# 5_SCS.net
KiCad netlist of a schematic drawn in Altium Designer
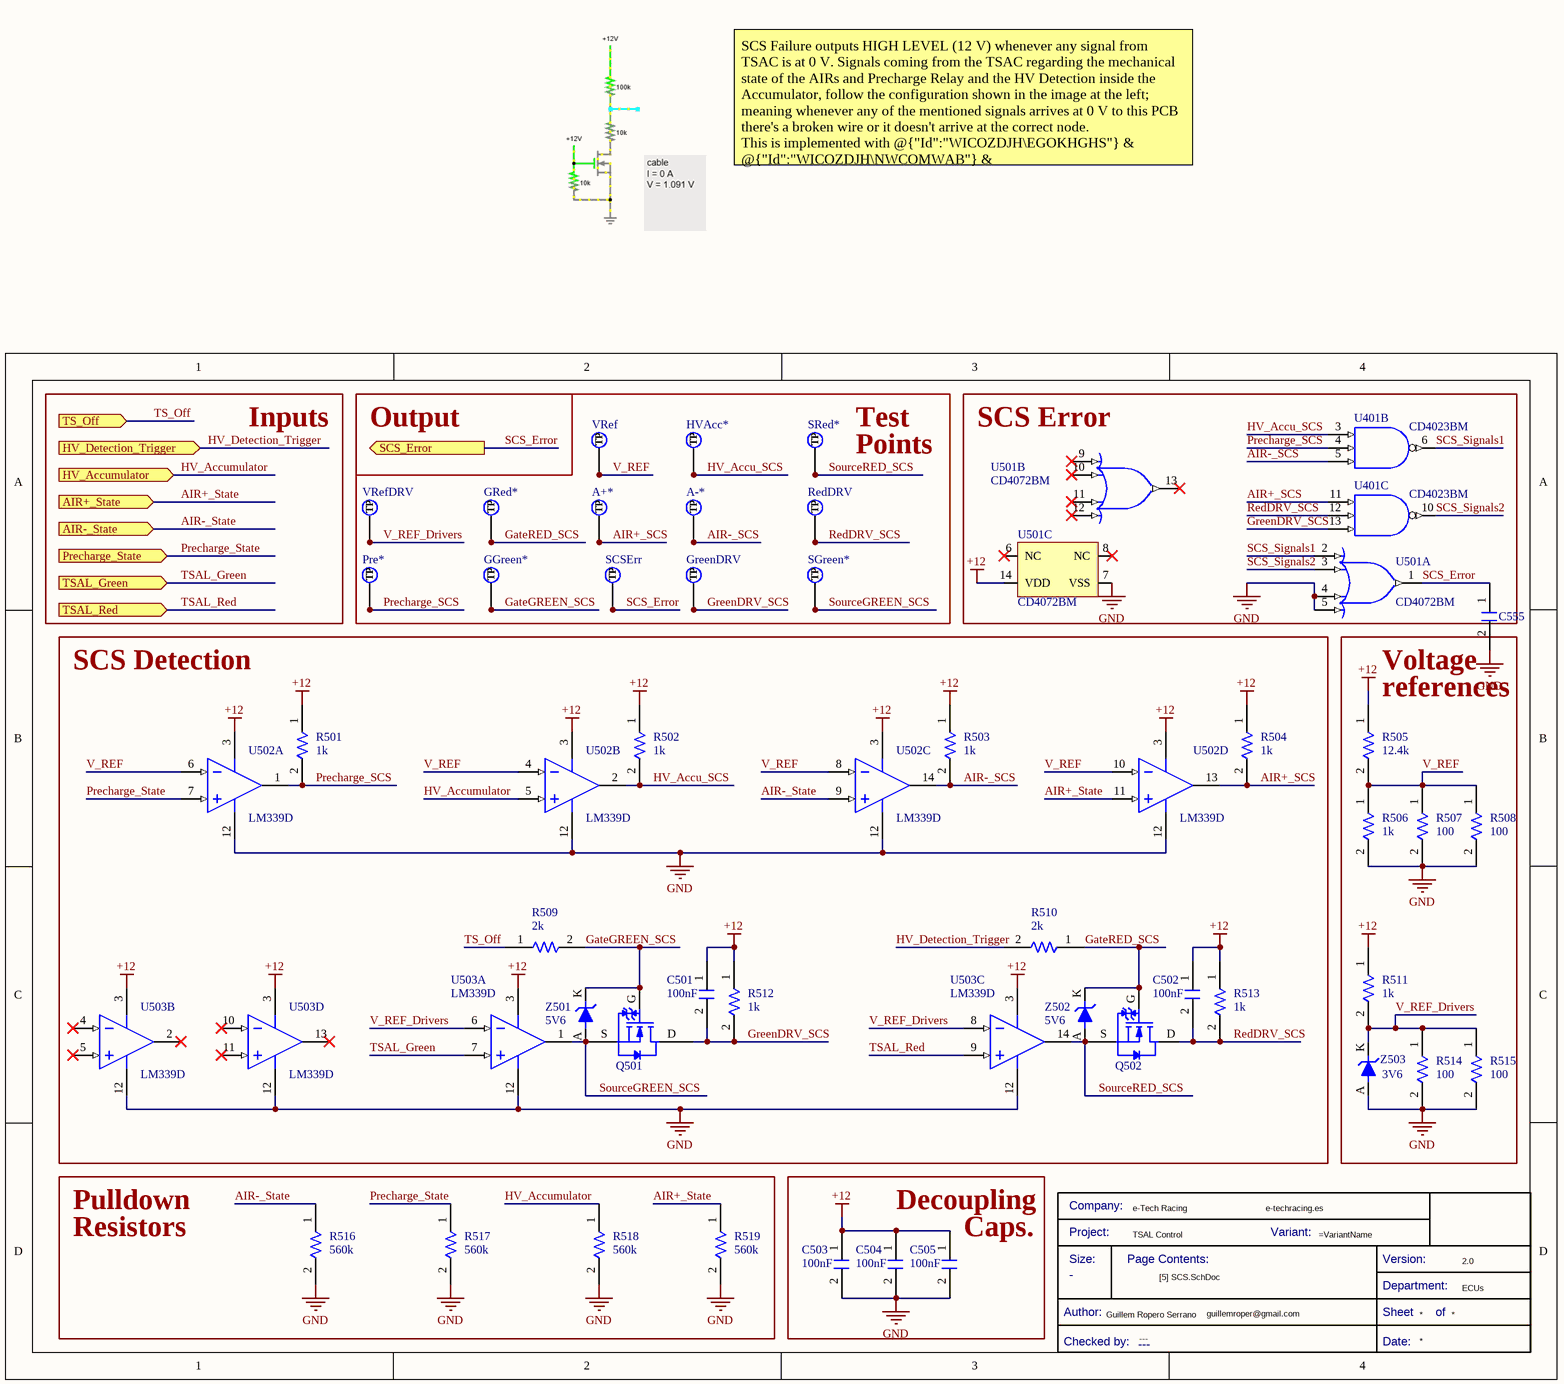
[diagram p0: [5] SCS.SchDoc]

(export (version "E")
  (design (tool "Eeschema 10.0.6"))
  (components
    (comp (ref "A+*")
      (value "TestPoint")
      (footprint "TestPoint")
      (description "Test Point 1x1 mm")
      (fields (field (name ".SCHCHECK") "GP") (field (name ".CREATOR") "GP") (field (name ".PCBCHECK") "GP"))
      (libsource (lib "EMEA- E-Tech Racing- I'Escola d'Enginyeria de Barcelona Est") (part "TestPoint"))
    )
    (comp (ref "A-*")
      (value "TestPoint")
      (footprint "TestPoint")
      (description "Test Point 1x1 mm")
      (fields (field (name ".SCHCHECK") "GP") (field (name ".CREATOR") "GP") (field (name ".PCBCHECK") "GP"))
      (libsource (lib "EMEA- E-Tech Racing- I'Escola d'Enginyeria de Barcelona Est") (part "TestPoint"))
    )
    (comp (ref "C501")
      (value "100nF")
      (footprint "C0805FNPC-R")
      (description "Cap, 0.1ΜF, 50V, 10%, X7R, 0805")
      (fields
        (field (name "TOLERANCE") "10%")
        (field (name "Comment") "C100n-50V-0805FNPC-X7R")
        (field (name ".CREATOR") "DR")
      )
      (libsource (lib "EMEA- E-Tech Racing- I'Escola d'Enginyeria de Barcelona Est") (part "C100p-50V-0805FNPC-C0G/NP0"))
    )
    (comp (ref "C502")
      (value "100nF")
      (footprint "C0805FNPC-R")
      (description "Cap, 0.1ΜF, 50V, 10%, X7R, 0805")
      (fields
        (field (name "TOLERANCE") "10%")
        (field (name "Comment") "C100n-50V-0805FNPC-X7R")
        (field (name ".CREATOR") "DR")
      )
      (libsource (lib "EMEA- E-Tech Racing- I'Escola d'Enginyeria de Barcelona Est") (part "C100p-50V-0805FNPC-C0G/NP0"))
    )
    (comp (ref "C503")
      (value "100nF")
      (footprint "C0805FNPC-R")
      (description "Cap, 0.1ΜF, 50V, 10%, X7R, 0805")
      (fields
        (field (name "TOLERANCE") "10%")
        (field (name "Comment") "C100n-50V-0805FNPC-X7R")
        (field (name ".CREATOR") "DR")
      )
      (libsource (lib "EMEA- E-Tech Racing- I'Escola d'Enginyeria de Barcelona Est") (part "C100p-50V-0805FNPC-C0G/NP0"))
    )
    (comp (ref "C504")
      (value "100nF")
      (footprint "C0805FNPC-R")
      (description "Cap, 0.1ΜF, 50V, 10%, X7R, 0805")
      (fields
        (field (name "TOLERANCE") "10%")
        (field (name "Comment") "C100n-50V-0805FNPC-X7R")
        (field (name ".CREATOR") "DR")
      )
      (libsource (lib "EMEA- E-Tech Racing- I'Escola d'Enginyeria de Barcelona Est") (part "C100p-50V-0805FNPC-C0G/NP0"))
    )
    (comp (ref "C505")
      (value "100nF")
      (footprint "C0805FNPC-R")
      (description "Cap, 0.1ΜF, 50V, 10%, X7R, 0805")
      (fields
        (field (name "TOLERANCE") "10%")
        (field (name "Comment") "C100n-50V-0805FNPC-X7R")
        (field (name ".CREATOR") "DR")
      )
      (libsource (lib "EMEA- E-Tech Racing- I'Escola d'Enginyeria de Barcelona Est") (part "C100p-50V-0805FNPC-C0G/NP0"))
    )
    (comp (ref "C555")
      (value "C15p-50V-0805FNPC-NP0")
      (footprint "C0805FNPC-R")
      (description "Cap, 15PF, 50V, 5%, C0G/NP0, 0805")
      (fields (field (name "TOLERANCE") "5%") (field (name ".CREATOR") "DR"))
      (libsource (lib "EMEA- E-Tech Racing- I'Escola d'Enginyeria de Barcelona Est") (part "C100p-50V-0805FNPC-C0G/NP0"))
    )
    (comp (ref "GGreen*")
      (value "TestPoint")
      (footprint "TestPoint")
      (description "Test Point 1x1 mm")
      (fields (field (name ".SCHCHECK") "GP") (field (name ".CREATOR") "GP") (field (name ".PCBCHECK") "GP"))
      (libsource (lib "EMEA- E-Tech Racing- I'Escola d'Enginyeria de Barcelona Est") (part "TestPoint"))
    )
    (comp (ref "GRed*")
      (value "TestPoint")
      (footprint "TestPoint")
      (description "Test Point 1x1 mm")
      (fields (field (name ".SCHCHECK") "GP") (field (name ".CREATOR") "GP") (field (name ".PCBCHECK") "GP"))
      (libsource (lib "EMEA- E-Tech Racing- I'Escola d'Enginyeria de Barcelona Est") (part "TestPoint"))
    )
    (comp (ref "GreenDRV")
      (value "TestPoint")
      (footprint "TestPoint")
      (description "Test Point 1x1 mm")
      (fields (field (name ".SCHCHECK") "GP") (field (name ".CREATOR") "GP") (field (name ".PCBCHECK") "GP"))
      (libsource (lib "EMEA- E-Tech Racing- I'Escola d'Enginyeria de Barcelona Est") (part "TestPoint"))
    )
    (comp (ref "HVAcc*")
      (value "TestPoint")
      (footprint "TestPoint")
      (description "Test Point 1x1 mm")
      (fields (field (name ".SCHCHECK") "GP") (field (name ".CREATOR") "GP") (field (name ".PCBCHECK") "GP"))
      (libsource (lib "EMEA- E-Tech Racing- I'Escola d'Enginyeria de Barcelona Est") (part "TestPoint"))
    )
    (comp (ref "Pre*")
      (value "TestPoint")
      (footprint "TestPoint")
      (description "Test Point 1x1 mm")
      (fields (field (name ".SCHCHECK") "GP") (field (name ".CREATOR") "GP") (field (name ".PCBCHECK") "GP"))
      (libsource (lib "EMEA- E-Tech Racing- I'Escola d'Enginyeria de Barcelona Est") (part "TestPoint"))
    )
    (comp (ref "Q501")
      (value "TRT-NCH-8/40-SQ")
      (footprint "TRT-NCH-3/35-CPH")
      (description "Automotive N-channel 40 V (d-s) 175C Mosfet SOT-23")
      (fields (field (name ".CREATOR") "DO"))
      (libsource (lib "EMEA- E-Tech Racing- I'Escola d'Enginyeria de Barcelona Est") (part "TRT-NCH-3/35-CPH"))
    )
    (comp (ref "Q502")
      (value "TRT-NCH-8/40-SQ")
      (footprint "TRT-NCH-3/35-CPH")
      (description "Automotive N-channel 40 V (d-s) 175C Mosfet SOT-23")
      (fields (field (name ".CREATOR") "DO"))
      (libsource (lib "EMEA- E-Tech Racing- I'Escola d'Enginyeria de Barcelona Est") (part "TRT-NCH-3/35-CPH"))
    )
    (comp (ref "R501")
      (value "1k")
      (footprint "R0805FTK")
      (description "Res Thick Film 0805 1K Ohm 5% 1/8W ±200ppm/°C Molded SMD SMD Paper Tape on Plastic Reel")
      (fields
        (field (name "TOLERANCE") "5%")
        (field (name "Comment") "R1k-0805FTK")
        (field (name ".CREATOR") "GP")
      )
      (libsource (lib "EMEA- E-Tech Racing- I'Escola d'Enginyeria de Barcelona Est") (part "CRCW08055K30FKTA"))
    )
    (comp (ref "R502")
      (value "1k")
      (footprint "R0805FTK")
      (description "Res Thick Film 0805 1K Ohm 5% 1/8W ±200ppm/°C Molded SMD SMD Paper Tape on Plastic Reel")
      (fields
        (field (name "TOLERANCE") "5%")
        (field (name "Comment") "R1k-0805FTK")
        (field (name ".CREATOR") "GP")
      )
      (libsource (lib "EMEA- E-Tech Racing- I'Escola d'Enginyeria de Barcelona Est") (part "CRCW08055K30FKTA"))
    )
    (comp (ref "R503")
      (value "1k")
      (footprint "R0805FTK")
      (description "Res Thick Film 0805 1K Ohm 5% 1/8W ±200ppm/°C Molded SMD SMD Paper Tape on Plastic Reel")
      (fields
        (field (name "TOLERANCE") "5%")
        (field (name "Comment") "R1k-0805FTK")
        (field (name ".CREATOR") "GP")
      )
      (libsource (lib "EMEA- E-Tech Racing- I'Escola d'Enginyeria de Barcelona Est") (part "CRCW08055K30FKTA"))
    )
    (comp (ref "R504")
      (value "1k")
      (footprint "R0805FTK")
      (description "Res Thick Film 0805 1K Ohm 5% 1/8W ±200ppm/°C Molded SMD SMD Paper Tape on Plastic Reel")
      (fields
        (field (name "TOLERANCE") "5%")
        (field (name "Comment") "R1k-0805FTK")
        (field (name ".CREATOR") "GP")
      )
      (libsource (lib "EMEA- E-Tech Racing- I'Escola d'Enginyeria de Barcelona Est") (part "CRCW08055K30FKTA"))
    )
    (comp (ref "R505")
      (value "12.4k")
      (footprint "0805")
      (fields
        (field (name "TOLERANCE") "1%")
        (field (name "POWER") "125mW")
        (field (name "Comment") "R12K4-0805-0.125W")
      )
      (libsource (lib "EMEA- E-Tech Racing- I'Escola d'Enginyeria de Barcelona Est") (part "R12K4-0805"))
    )
    (comp (ref "R506")
      (value "1k")
      (footprint "0805")
      (fields
        (field (name "TOLERANCE") "1%")
        (field (name "POWER") "500mW")
        (field (name "Comment") "R1K-0805-0.5W")
      )
      (libsource (lib "EMEA- E-Tech Racing- I'Escola d'Enginyeria de Barcelona Est") (part "R1k-0805"))
    )
    (comp (ref "R507")
      (value "100")
      (footprint "R0805FTK")
      (description "Res Thick Film 0805 100 Ohm 1% 1/8W ±100ppm/°C Molded SMD SMD Paper Tape on Plastic Reel")
      (fields
        (field (name "TOLERANCE") "1%")
        (field (name "Comment") "R100-0805FTK")
        (field (name ".CREATOR") "DR")
      )
      (libsource (lib "EMEA- E-Tech Racing- I'Escola d'Enginyeria de Barcelona Est") (part "CRCW08055K30FKTA"))
    )
    (comp (ref "R508")
      (value "100")
      (footprint "R0805FTK")
      (description "Res Thick Film 0805 100 Ohm 1% 1/8W ±100ppm/°C Molded SMD SMD Paper Tape on Plastic Reel")
      (fields
        (field (name "TOLERANCE") "1%")
        (field (name "Comment") "R100-0805FTK")
        (field (name ".CREATOR") "DR")
      )
      (libsource (lib "EMEA- E-Tech Racing- I'Escola d'Enginyeria de Barcelona Est") (part "CRCW08055K30FKTA"))
    )
    (comp (ref "R509")
      (value "2k")
      (footprint "0805")
      (fields
        (field (name "POWER") "500mW")
        (field (name "MANUFACTURER") "Vishay")
        (field (name "TOLERANCE") "1%")
      )
      (libsource (lib "EMEA- E-Tech Racing- I'Escola d'Enginyeria de Barcelona Est") (part "R9.09K-1206FTK"))
    )
    (comp (ref "R510")
      (value "2k")
      (footprint "0805")
      (fields
        (field (name "POWER") "500mW")
        (field (name "MANUFACTURER") "Vishay")
        (field (name "TOLERANCE") "1%")
      )
      (libsource (lib "EMEA- E-Tech Racing- I'Escola d'Enginyeria de Barcelona Est") (part "R9.09K-1206FTK"))
    )
    (comp (ref "R511")
      (value "1k")
      (footprint "0805")
      (fields
        (field (name "TOLERANCE") "1%")
        (field (name "POWER") "500mW")
        (field (name "Comment") "R1K-0805-0.5W")
      )
      (libsource (lib "EMEA- E-Tech Racing- I'Escola d'Enginyeria de Barcelona Est") (part "R1k-0805"))
    )
    (comp (ref "R512")
      (value "1k")
      (footprint "R0805FTK")
      (description "Res Thick Film 0805 1K Ohm 5% 1/8W ±200ppm/°C Molded SMD SMD Paper Tape on Plastic Reel")
      (fields
        (field (name "TOLERANCE") "5%")
        (field (name "Comment") "R1k-0805FTK")
        (field (name ".CREATOR") "GP")
      )
      (libsource (lib "EMEA- E-Tech Racing- I'Escola d'Enginyeria de Barcelona Est") (part "CRCW08055K30FKTA"))
    )
    (comp (ref "R513")
      (value "1k")
      (footprint "R0805FTK")
      (description "Res Thick Film 0805 1K Ohm 5% 1/8W ±200ppm/°C Molded SMD SMD Paper Tape on Plastic Reel")
      (fields
        (field (name "TOLERANCE") "5%")
        (field (name "Comment") "R1k-0805FTK")
        (field (name ".CREATOR") "GP")
      )
      (libsource (lib "EMEA- E-Tech Racing- I'Escola d'Enginyeria de Barcelona Est") (part "CRCW08055K30FKTA"))
    )
    (comp (ref "R514")
      (value "100")
      (footprint "R0805FTK")
      (description "Res Thick Film 0805 100 Ohm 1% 1/8W ±100ppm/°C Molded SMD SMD Paper Tape on Plastic Reel")
      (fields
        (field (name "TOLERANCE") "1%")
        (field (name "Comment") "R100-0805FTK")
        (field (name ".CREATOR") "DR")
      )
      (libsource (lib "EMEA- E-Tech Racing- I'Escola d'Enginyeria de Barcelona Est") (part "CRCW08055K30FKTA"))
    )
    (comp (ref "R515")
      (value "100")
      (footprint "R0805FTK")
      (description "Res Thick Film 0805 100 Ohm 1% 1/8W ±100ppm/°C Molded SMD SMD Paper Tape on Plastic Reel")
      (fields
        (field (name "TOLERANCE") "1%")
        (field (name "Comment") "R100-0805FTK")
        (field (name ".CREATOR") "DR")
      )
      (libsource (lib "EMEA- E-Tech Racing- I'Escola d'Enginyeria de Barcelona Est") (part "CRCW08055K30FKTA"))
    )
    (comp (ref "R516")
      (value "560k")
      (footprint "0805")
      (fields
        (field (name "POWER") "125mW")
        (field (name "TOLERANCE") "1%")
        (field (name "Comment") "R560K-0805")
      )
      (libsource (lib "EMEA- E-Tech Racing- I'Escola d'Enginyeria de Barcelona Est") (part "CRCW08055K30FKTA"))
    )
    (comp (ref "R517")
      (value "560k")
      (footprint "0805")
      (fields
        (field (name "POWER") "125mW")
        (field (name "TOLERANCE") "1%")
        (field (name "Comment") "R560K-0805")
      )
      (libsource (lib "EMEA- E-Tech Racing- I'Escola d'Enginyeria de Barcelona Est") (part "CRCW08055K30FKTA"))
    )
    (comp (ref "R518")
      (value "560k")
      (footprint "0805")
      (fields
        (field (name "POWER") "125mW")
        (field (name "TOLERANCE") "1%")
        (field (name "Comment") "R560K-0805")
      )
      (libsource (lib "EMEA- E-Tech Racing- I'Escola d'Enginyeria de Barcelona Est") (part "CRCW08055K30FKTA"))
    )
    (comp (ref "R519")
      (value "560k")
      (footprint "0805")
      (fields
        (field (name "POWER") "125mW")
        (field (name "TOLERANCE") "1%")
        (field (name "Comment") "R560K-0805")
      )
      (libsource (lib "EMEA- E-Tech Racing- I'Escola d'Enginyeria de Barcelona Est") (part "CRCW08055K30FKTA"))
    )
    (comp (ref "RedDRV")
      (value "TestPoint")
      (footprint "TestPoint")
      (description "Test Point 1x1 mm")
      (fields (field (name ".SCHCHECK") "GP") (field (name ".CREATOR") "GP") (field (name ".PCBCHECK") "GP"))
      (libsource (lib "EMEA- E-Tech Racing- I'Escola d'Enginyeria de Barcelona Est") (part "TestPoint"))
    )
    (comp (ref "SCSErr")
      (value "TestPoint")
      (footprint "TestPoint")
      (description "Test Point 1x1 mm")
      (fields (field (name ".SCHCHECK") "GP") (field (name ".CREATOR") "GP") (field (name ".PCBCHECK") "GP"))
      (libsource (lib "EMEA- E-Tech Racing- I'Escola d'Enginyeria de Barcelona Est") (part "TestPoint"))
    )
    (comp (ref "SGreen*")
      (value "TestPoint")
      (footprint "TestPoint")
      (description "Test Point 1x1 mm")
      (fields (field (name ".SCHCHECK") "GP") (field (name ".CREATOR") "GP") (field (name ".PCBCHECK") "GP"))
      (libsource (lib "EMEA- E-Tech Racing- I'Escola d'Enginyeria de Barcelona Est") (part "TestPoint"))
    )
    (comp (ref "SRed*")
      (value "TestPoint")
      (footprint "TestPoint")
      (description "Test Point 1x1 mm")
      (fields (field (name ".SCHCHECK") "GP") (field (name ".CREATOR") "GP") (field (name ".PCBCHECK") "GP"))
      (libsource (lib "EMEA- E-Tech Racing- I'Escola d'Enginyeria de Barcelona Est") (part "TestPoint"))
    )
    (comp (ref "U401")
      (value "CD4023BM")
      (footprint "D0014A_N")
      (description "NAND Gate, 4000/14000/40000 Series, 3-Func, 3-Input, CMOS, CDIP14")
      (libsource (lib "EMEA- E-Tech Racing- I'Escola d'Enginyeria de Barcelona Est") (part "TI-CD4023B-D0014A-14"))
    )
    (comp (ref "U501")
      (value "CD4072BM")
      (footprint "D0014A_N")
      (description "OR Gate, 4000/14000/40000 Series, 2-Func, 4-Input, CMOS, PDSO14")
      (libsource (lib "EMEA- E-Tech Racing- I'Escola d'Enginyeria de Barcelona Est") (part "TI-CD4072B-14"))
    )
    (comp (ref "U502")
      (value "LM339D")
      (footprint "D0014A_N")
      (description "Comparator, 4 Func, 5000uV Offset-Max, 300ns Response Time, BIPolar, PDSO14")
      (libsource (lib "EMEA- E-Tech Racing- I'Escola d'Enginyeria de Barcelona Est") (part "TI-LMXXXX14"))
    )
    (comp (ref "U503")
      (value "LM339D")
      (footprint "D0014A_N")
      (description "Comparator, 4 Func, 5000uV Offset-Max, 300ns Response Time, BIPolar, PDSO14")
      (libsource (lib "EMEA- E-Tech Racing- I'Escola d'Enginyeria de Barcelona Est") (part "TI-LMXXXX14"))
    )
    (comp (ref "VRef")
      (value "TestPoint")
      (footprint "TestPoint")
      (description "Test Point 1x1 mm")
      (fields (field (name ".SCHCHECK") "GP") (field (name ".CREATOR") "GP") (field (name ".PCBCHECK") "GP"))
      (libsource (lib "EMEA- E-Tech Racing- I'Escola d'Enginyeria de Barcelona Est") (part "TestPoint"))
    )
    (comp (ref "VRefDRV")
      (value "TestPoint")
      (footprint "TestPoint")
      (description "Test Point 1x1 mm")
      (fields (field (name ".SCHCHECK") "GP") (field (name ".CREATOR") "GP") (field (name ".PCBCHECK") "GP"))
      (libsource (lib "EMEA- E-Tech Racing- I'Escola d'Enginyeria de Barcelona Est") (part "TestPoint"))
    )
    (comp (ref "Z501")
      (value "DZ-5.6V-DO-214AC")
      (footprint "DO-214AC")
      (description "Zener Diode, 5.6V V(Z), 5%, 0.5W, Silicon, Unidirectional, DO-214AC")
      (fields (field (name "ZENER VOLTAGE") "5V6"))
      (libsource (lib "EMEA- E-Tech Racing- I'Escola d'Enginyeria de Barcelona Est") (part "DZ-0.01/75-SOD-123"))
    )
    (comp (ref "Z502")
      (value "DZ-5.6V-DO-214AC")
      (footprint "DO-214AC")
      (description "Zener Diode, 5.6V V(Z), 5%, 0.5W, Silicon, Unidirectional, DO-214AC")
      (fields (field (name "ZENER VOLTAGE") "5V6"))
      (libsource (lib "EMEA- E-Tech Racing- I'Escola d'Enginyeria de Barcelona Est") (part "DZ-0.01/75-SOD-123"))
    )
    (comp (ref "Z503")
      (value "DZ-3V6-1.25W-DO-214AC")
      (footprint "DZ-DO-214AC")
      (description "Zener Diode, 3.6V V(Z), 5.56%, 1.25W, Silicon, Unidirectional, DO-214AC, BZG05C3V6-M3-08")
      (fields (field (name "ZENER VOLTAGE") "3V6"))
      (libsource (lib "EMEA- E-Tech Racing- I'Escola d'Enginyeria de Barcelona Est") (part "DZENER-DO-214AC"))
    )
  )
  (nets
    (net (code "1") (name "+12") (class "Default")
      (node (ref "C501") (pin "1") (pinfunction "1_1") (pintype "passive"))
      (node (ref "C502") (pin "1") (pinfunction "1_1") (pintype "passive"))
      (node (ref "C503") (pin "1") (pinfunction "1_1") (pintype "passive"))
      (node (ref "C504") (pin "1") (pinfunction "1_1") (pintype "passive"))
      (node (ref "C505") (pin "1") (pinfunction "1_1") (pintype "passive"))
      (node (ref "R501") (pin "1") (pinfunction "1_1") (pintype "passive"))
      (node (ref "R502") (pin "1") (pinfunction "1_1") (pintype "passive"))
      (node (ref "R503") (pin "1") (pinfunction "1_1") (pintype "passive"))
      (node (ref "R504") (pin "1") (pinfunction "1_1") (pintype "passive"))
      (node (ref "R505") (pin "1") (pinfunction "1_1") (pintype "passive"))
      (node (ref "R511") (pin "1") (pinfunction "1_1") (pintype "passive"))
      (node (ref "R512") (pin "1") (pinfunction "1_1") (pintype "passive"))
      (node (ref "R513") (pin "1") (pinfunction "1_1") (pintype "passive"))
      (node (ref "U501") (pin "14") (pinfunction "VDD_14") (pintype "power_in"))
      (node (ref "U502") (pin "3") (pinfunction "VCC_3") (pintype "power_in"))
      (node (ref "U503") (pin "3") (pinfunction "VCC_3") (pintype "power_in"))
    )
    (net (code "2") (name "/AIR+_SCS") (class "Default")
      (node (ref "A+*") (pin "1") (pinfunction "TP_1") (pintype "passive"))
      (node (ref "R504") (pin "2") (pinfunction "2_2") (pintype "passive"))
      (node (ref "U401") (pin "11") (pinfunction "I_11") (pintype "input"))
      (node (ref "U502") (pin "13") (pinfunction "OUT4_13") (pintype "open_collector"))
    )
    (net (code "3") (name "/AIR+_State") (class "Default")
      (node (ref "R519") (pin "1") (pinfunction "1_1") (pintype "passive"))
      (node (ref "U502") (pin "11") (pinfunction "IN4+_11") (pintype "input"))
    )
    (net (code "4") (name "/AIR-_SCS") (class "Default")
      (node (ref "A-*") (pin "1") (pinfunction "TP_1") (pintype "passive"))
      (node (ref "R503") (pin "2") (pinfunction "2_2") (pintype "passive"))
      (node (ref "U401") (pin "5") (pinfunction "F_5") (pintype "input"))
      (node (ref "U502") (pin "14") (pinfunction "OUT3_14") (pintype "open_collector"))
    )
    (net (code "5") (name "/AIR-_State") (class "Default")
      (node (ref "R516") (pin "1") (pinfunction "1_1") (pintype "passive"))
      (node (ref "U502") (pin "9") (pinfunction "IN3+_9") (pintype "input"))
    )
    (net (code "6") (name "/GateGREEN_SCS") (class "Default")
      (node (ref "GGreen*") (pin "1") (pinfunction "TP_1") (pintype "passive"))
      (node (ref "Q501") (pin "G") (pinfunction "G_G") (pintype "passive"))
      (node (ref "R509") (pin "2") (pinfunction "2_2") (pintype "passive"))
      (node (ref "Z501") (pin "K") (pinfunction "K_K") (pintype "passive"))
    )
    (net (code "7") (name "/GateRED_SCS") (class "Default")
      (node (ref "GRed*") (pin "1") (pinfunction "TP_1") (pintype "passive"))
      (node (ref "Q502") (pin "G") (pinfunction "G_G") (pintype "passive"))
      (node (ref "R510") (pin "1") (pinfunction "1_1") (pintype "passive"))
      (node (ref "Z502") (pin "K") (pinfunction "K_K") (pintype "passive"))
    )
    (net (code "8") (name "/GreenDRV_SCS") (class "Default")
      (node (ref "C501") (pin "2") (pinfunction "2_2") (pintype "passive"))
      (node (ref "GreenDRV") (pin "1") (pinfunction "TP_1") (pintype "passive"))
      (node (ref "Q501") (pin "D") (pinfunction "D_D") (pintype "passive"))
      (node (ref "R512") (pin "2") (pinfunction "2_2") (pintype "passive"))
      (node (ref "U401") (pin "13") (pinfunction "G_13") (pintype "input"))
    )
    (net (code "9") (name "/HV_Accu_SCS") (class "Default")
      (node (ref "HVAcc*") (pin "1") (pinfunction "TP_1") (pintype "passive"))
      (node (ref "R502") (pin "2") (pinfunction "2_2") (pintype "passive"))
      (node (ref "U401") (pin "3") (pinfunction "D_3") (pintype "input"))
      (node (ref "U502") (pin "2") (pinfunction "OUT2_2") (pintype "open_collector"))
    )
    (net (code "10") (name "/HV_Accumulator") (class "Default")
      (node (ref "R518") (pin "1") (pinfunction "1_1") (pintype "passive"))
      (node (ref "U502") (pin "5") (pinfunction "IN2+_5") (pintype "input"))
    )
    (net (code "11") (name "/HV_Detection_Trigger") (class "Default")
      (node (ref "R510") (pin "2") (pinfunction "2_2") (pintype "passive"))
    )
    (net (code "12") (name "/Precharge_SCS") (class "Default")
      (node (ref "Pre*") (pin "1") (pinfunction "TP_1") (pintype "passive"))
      (node (ref "R501") (pin "2") (pinfunction "2_2") (pintype "passive"))
      (node (ref "U401") (pin "4") (pinfunction "E_4") (pintype "input"))
      (node (ref "U502") (pin "1") (pinfunction "OUT1_1") (pintype "open_collector"))
    )
    (net (code "13") (name "/Precharge_State") (class "Default")
      (node (ref "R517") (pin "1") (pinfunction "1_1") (pintype "passive"))
      (node (ref "U502") (pin "7") (pinfunction "IN1+_7") (pintype "input"))
    )
    (net (code "14") (name "/RedDRV_SCS") (class "Default")
      (node (ref "C502") (pin "2") (pinfunction "2_2") (pintype "passive"))
      (node (ref "Q502") (pin "D") (pinfunction "D_D") (pintype "passive"))
      (node (ref "R513") (pin "2") (pinfunction "2_2") (pintype "passive"))
      (node (ref "RedDRV") (pin "1") (pinfunction "TP_1") (pintype "passive"))
      (node (ref "U401") (pin "12") (pinfunction "H_12") (pintype "input"))
    )
    (net (code "15") (name "/SCS_Error") (class "Default")
      (node (ref "C555") (pin "1") (pinfunction "1_1") (pintype "passive"))
      (node (ref "SCSErr") (pin "1") (pinfunction "TP_1") (pintype "passive"))
      (node (ref "U501") (pin "1") (pinfunction "J_1") (pintype "output"))
    )
    (net (code "16") (name "/SCS_Signals1") (class "Default")
      (node (ref "U401") (pin "6") (pinfunction "K_6") (pintype "output"))
      (node (ref "U501") (pin "2") (pinfunction "A_2") (pintype "input"))
    )
    (net (code "17") (name "/SCS_Signals2") (class "Default")
      (node (ref "U401") (pin "10") (pinfunction "L_10") (pintype "output"))
      (node (ref "U501") (pin "3") (pinfunction "B_3") (pintype "input"))
    )
    (net (code "18") (name "/SourceGREEN_SCS") (class "Default")
      (node (ref "Q501") (pin "S") (pinfunction "S_S") (pintype "passive"))
      (node (ref "SGreen*") (pin "1") (pinfunction "TP_1") (pintype "passive"))
      (node (ref "U503") (pin "1") (pinfunction "OUT1_1") (pintype "open_collector"))
      (node (ref "Z501") (pin "A") (pinfunction "A_A") (pintype "passive"))
    )
    (net (code "19") (name "/SourceRED_SCS") (class "Default")
      (node (ref "Q502") (pin "S") (pinfunction "S_S") (pintype "passive"))
      (node (ref "SRed*") (pin "1") (pinfunction "TP_1") (pintype "passive"))
      (node (ref "U503") (pin "14") (pinfunction "OUT3_14") (pintype "open_collector"))
      (node (ref "Z502") (pin "A") (pinfunction "A_A") (pintype "passive"))
    )
    (net (code "20") (name "/TSAL_Green") (class "Default")
      (node (ref "U503") (pin "7") (pinfunction "IN1+_7") (pintype "input"))
    )
    (net (code "21") (name "/TSAL_Red") (class "Default")
      (node (ref "U503") (pin "9") (pinfunction "IN3+_9") (pintype "input"))
    )
    (net (code "22") (name "/TS_Off") (class "Default")
      (node (ref "R509") (pin "1") (pinfunction "1_1") (pintype "passive"))
    )
    (net (code "23") (name "/V_REF") (class "Default")
      (node (ref "R505") (pin "2") (pinfunction "2_2") (pintype "passive"))
      (node (ref "R506") (pin "1") (pinfunction "1_1") (pintype "passive"))
      (node (ref "R507") (pin "1") (pinfunction "1_1") (pintype "passive"))
      (node (ref "R508") (pin "1") (pinfunction "1_1") (pintype "passive"))
      (node (ref "U502") (pin "10") (pinfunction "IN4-_10") (pintype "input"))
      (node (ref "U502") (pin "4") (pinfunction "IN2-_4") (pintype "input"))
      (node (ref "U502") (pin "6") (pinfunction "IN1-_6") (pintype "input"))
      (node (ref "U502") (pin "8") (pinfunction "IN3-_8") (pintype "input"))
      (node (ref "VRef") (pin "1") (pinfunction "TP_1") (pintype "passive"))
    )
    (net (code "24") (name "/V_REF_Drivers") (class "Default")
      (node (ref "R511") (pin "2") (pinfunction "2_2") (pintype "passive"))
      (node (ref "R514") (pin "1") (pinfunction "1_1") (pintype "passive"))
      (node (ref "R515") (pin "1") (pinfunction "1_1") (pintype "passive"))
      (node (ref "U503") (pin "6") (pinfunction "IN1-_6") (pintype "input"))
      (node (ref "U503") (pin "8") (pinfunction "IN3-_8") (pintype "input"))
      (node (ref "VRefDRV") (pin "1") (pinfunction "TP_1") (pintype "passive"))
      (node (ref "Z503") (pin "K") (pinfunction "K_K") (pintype "passive"))
    )
    (net (code "25") (name "GND") (class "Default")
      (node (ref "C503") (pin "2") (pinfunction "2_2") (pintype "passive"))
      (node (ref "C504") (pin "2") (pinfunction "2_2") (pintype "passive"))
      (node (ref "C505") (pin "2") (pinfunction "2_2") (pintype "passive"))
      (node (ref "C555") (pin "2") (pinfunction "2_2") (pintype "passive"))
      (node (ref "R506") (pin "2") (pinfunction "2_2") (pintype "passive"))
      (node (ref "R507") (pin "2") (pinfunction "2_2") (pintype "passive"))
      (node (ref "R508") (pin "2") (pinfunction "2_2") (pintype "passive"))
      (node (ref "R514") (pin "2") (pinfunction "2_2") (pintype "passive"))
      (node (ref "R515") (pin "2") (pinfunction "2_2") (pintype "passive"))
      (node (ref "R516") (pin "2") (pinfunction "2_2") (pintype "passive"))
      (node (ref "R517") (pin "2") (pinfunction "2_2") (pintype "passive"))
      (node (ref "R518") (pin "2") (pinfunction "2_2") (pintype "passive"))
      (node (ref "R519") (pin "2") (pinfunction "2_2") (pintype "passive"))
      (node (ref "U501") (pin "4") (pinfunction "C_4") (pintype "input"))
      (node (ref "U501") (pin "5") (pinfunction "D_5") (pintype "input"))
      (node (ref "U501") (pin "7") (pinfunction "VSS_7") (pintype "power_in"))
      (node (ref "U502") (pin "12") (pinfunction "GND_12") (pintype "power_in"))
      (node (ref "U503") (pin "12") (pinfunction "GND_12") (pintype "power_in"))
      (node (ref "Z503") (pin "A") (pinfunction "A_A") (pintype "passive"))
    )
    (net (code "26") (name "unconnected-(U501B-E-Pad9)") (class "Default")
      (node (ref "U501") (pin "9") (pinfunction "E_9") (pintype "input+no_connect"))
    )
    (net (code "27") (name "unconnected-(U501B-F-Pad10)") (class "Default")
      (node (ref "U501") (pin "10") (pinfunction "F_10") (pintype "input+no_connect"))
    )
    (net (code "28") (name "unconnected-(U501B-G-Pad11)") (class "Default")
      (node (ref "U501") (pin "11") (pinfunction "G_11") (pintype "input+no_connect"))
    )
    (net (code "29") (name "unconnected-(U501B-H-Pad12)") (class "Default")
      (node (ref "U501") (pin "12") (pinfunction "H_12") (pintype "input+no_connect"))
    )
    (net (code "30") (name "unconnected-(U501B-K-Pad13)") (class "Default")
      (node (ref "U501") (pin "13") (pinfunction "K_13") (pintype "output+no_connect"))
    )
    (net (code "31") (name "unconnected-(U501C-NC-Pad6)") (class "Default")
      (node (ref "U501") (pin "6") (pinfunction "NC_6") (pintype "passive+no_connect"))
    )
    (net (code "32") (name "unconnected-(U501C-NC-Pad8)") (class "Default")
      (node (ref "U501") (pin "8") (pinfunction "NC_8") (pintype "passive+no_connect"))
    )
    (net (code "33") (name "unconnected-(U503B-IN2+-Pad5)") (class "Default")
      (node (ref "U503") (pin "5") (pinfunction "IN2+_5") (pintype "input+no_connect"))
    )
    (net (code "34") (name "unconnected-(U503B-IN2--Pad4)") (class "Default")
      (node (ref "U503") (pin "4") (pinfunction "IN2-_4") (pintype "input+no_connect"))
    )
    (net (code "35") (name "unconnected-(U503B-OUT2-Pad2)") (class "Default")
      (node (ref "U503") (pin "2") (pinfunction "OUT2_2") (pintype "open_collector+no_connect"))
    )
    (net (code "36") (name "unconnected-(U503D-IN4+-Pad11)") (class "Default")
      (node (ref "U503") (pin "11") (pinfunction "IN4+_11") (pintype "input+no_connect"))
    )
    (net (code "37") (name "unconnected-(U503D-IN4--Pad10)") (class "Default")
      (node (ref "U503") (pin "10") (pinfunction "IN4-_10") (pintype "input+no_connect"))
    )
    (net (code "38") (name "unconnected-(U503D-OUT4-Pad13)") (class "Default")
      (node (ref "U503") (pin "13") (pinfunction "OUT4_13") (pintype "open_collector+no_connect"))
    )
  )
)
